# SELE_async_v0_1.net
KiCad netlist of a schematic drawn in EasyEDA
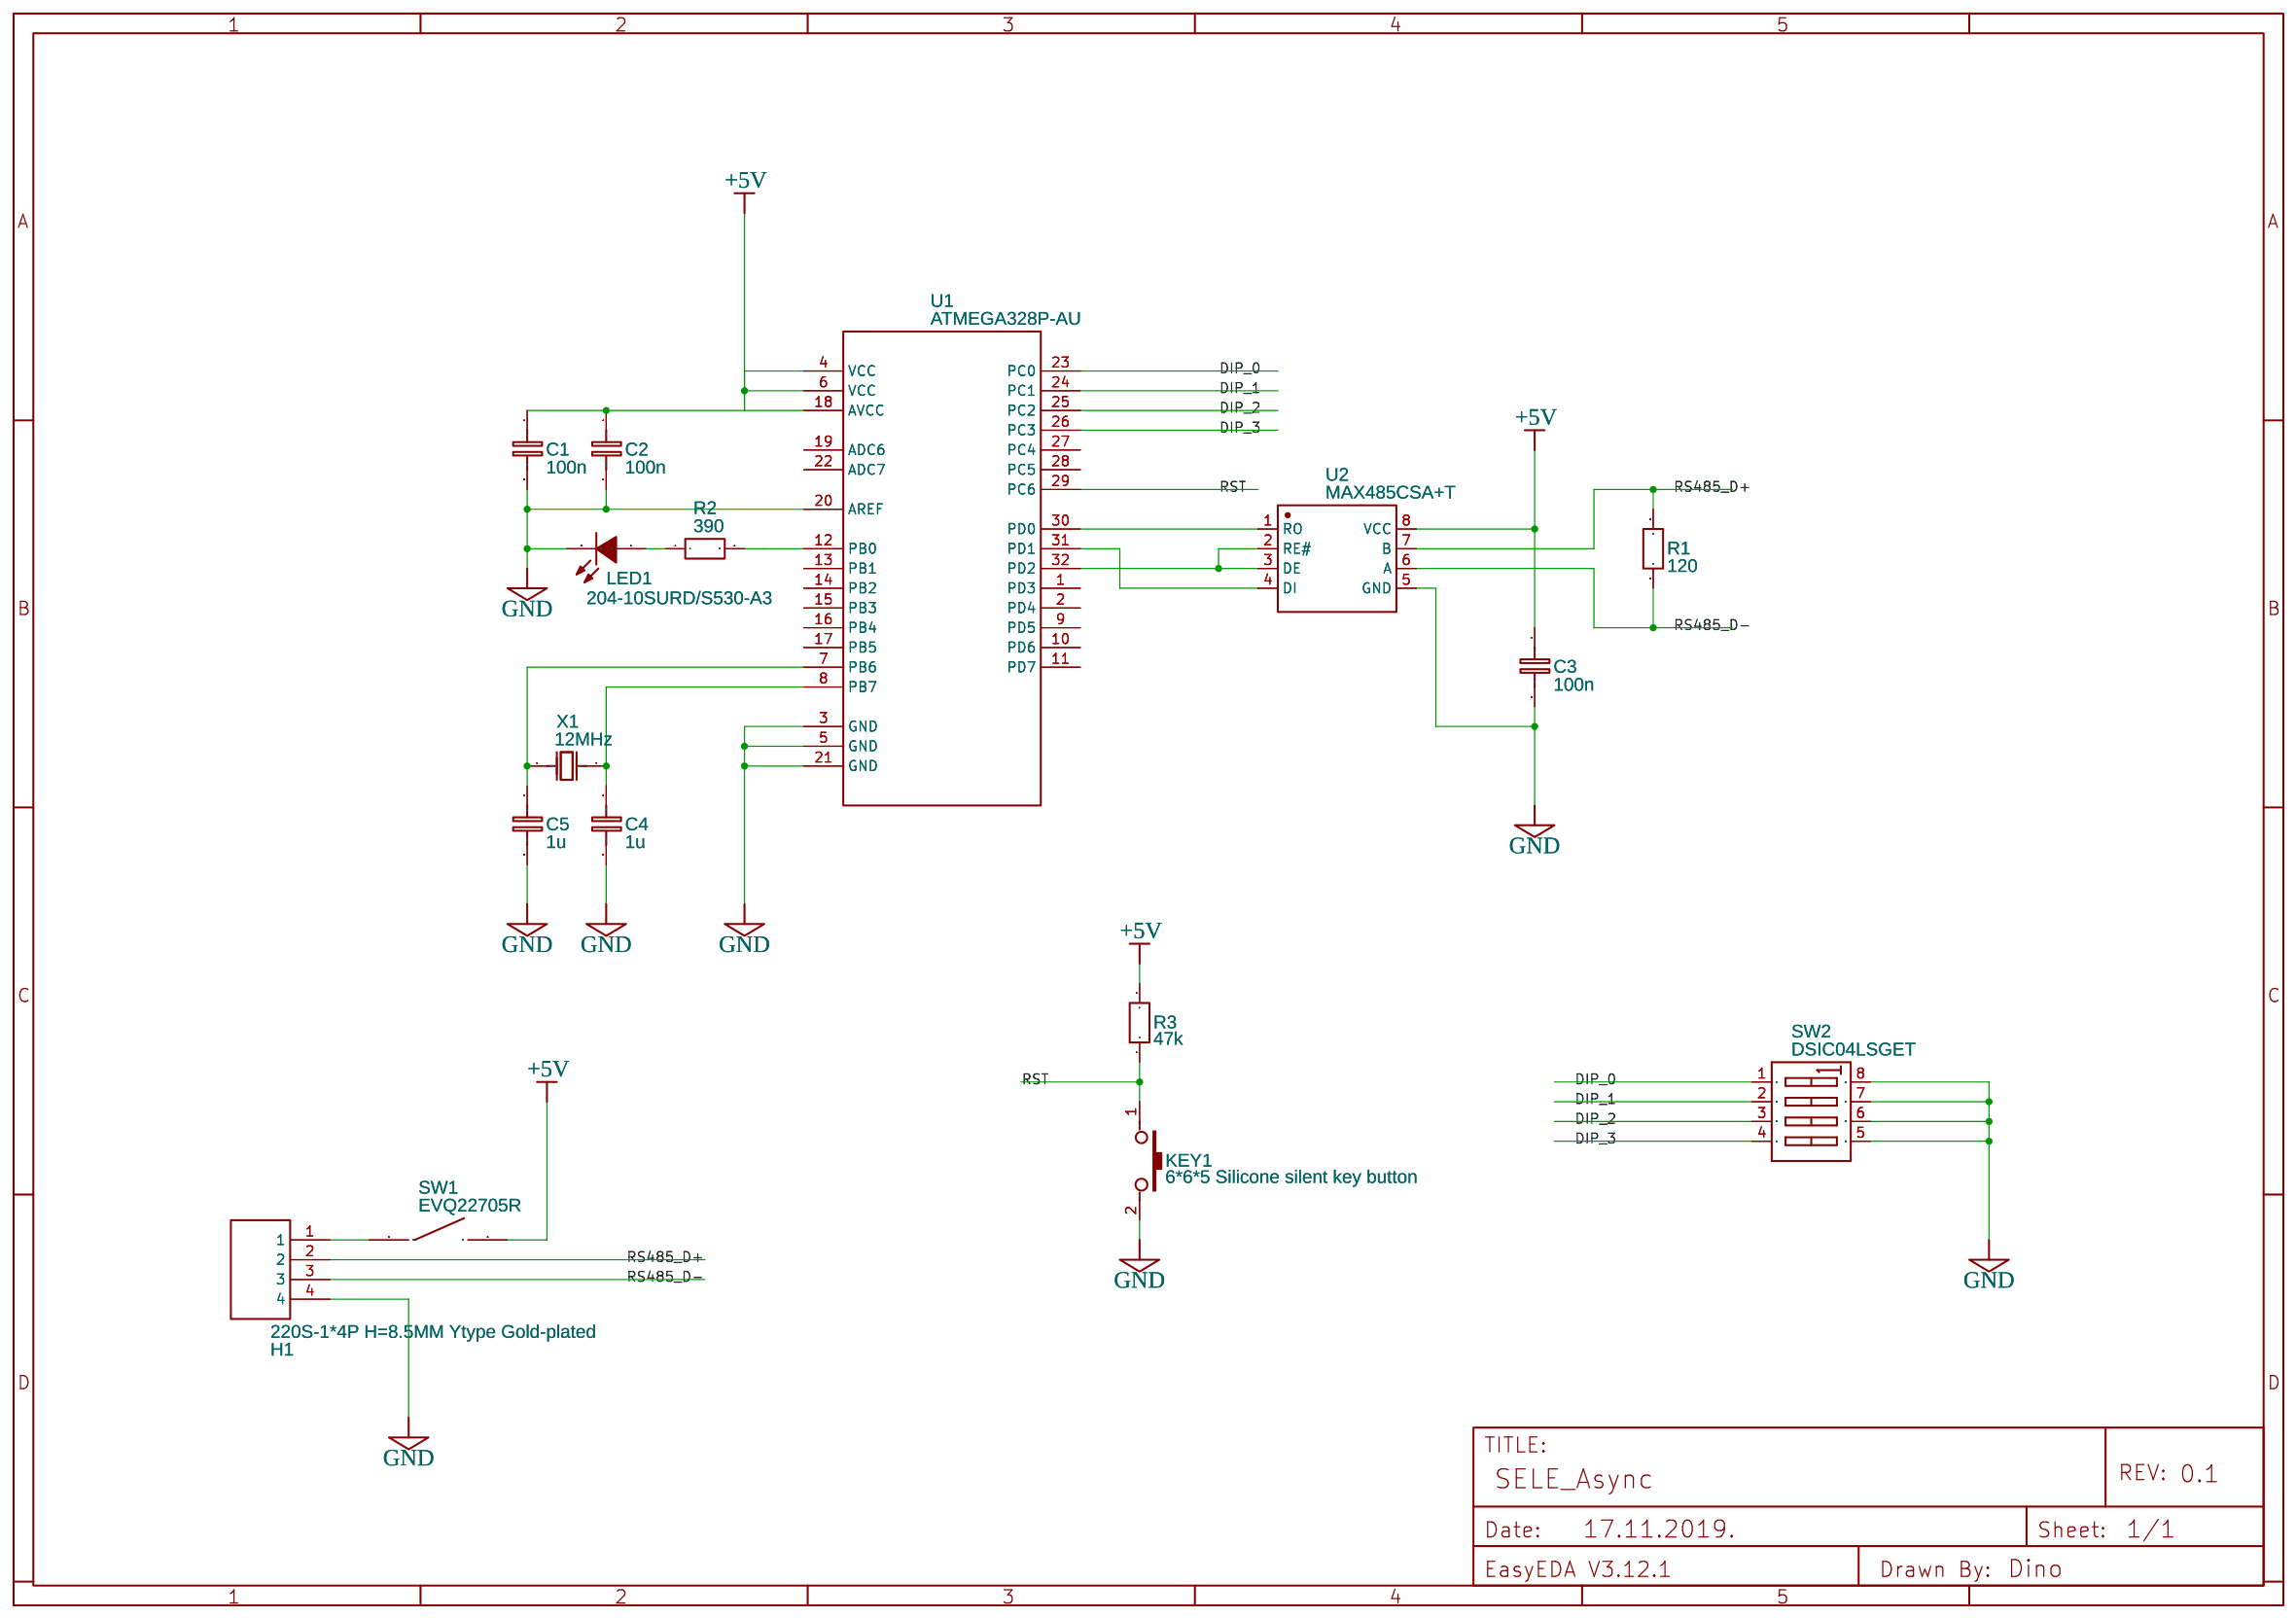
[diagram p0: schematic sheet]

(export (version "E")
  (design (tool "Eeschema 10.0.6"))
  (components
    (comp (ref "C1") (value "100n") (libsource (lib "") (part "Cap_0603_EU")))
    (comp (ref "C2") (value "100n") (libsource (lib "") (part "Cap_0603_EU")))
    (comp (ref "C3") (value "100n") (libsource (lib "") (part "Cap_0603_EU_1")))
    (comp (ref "C4") (value "1u") (libsource (lib "") (part "Cap_0603_EU")))
    (comp (ref "C5") (value "1u") (libsource (lib "") (part "Cap_0603_EU")))
    (comp (ref "H1")
      (value "220S-1*4P H=8.5MM Ytype Gold-plated")
      (fields (field (name "BOM_Supplier Part") "C124413"))
      (libsource (lib "") (part "Unknown_180_670"))
    )
    (comp (ref "KEY1")
      (value "6*6*5 Silicone silent key button")
      (fields (field (name "BOM_Supplier Part") "C61120"))
      (libsource (lib "") (part "Unknown_620_610"))
    )
    (comp (ref "LED1")
      (value "204-10SURD/S530-A3")
      (fields (field (name "BOM_Supplier Part") "C99772"))
      (libsource (lib "") (part "Unknown_350_300"))
    )
    (comp (ref "R1") (value "120") (libsource (lib "") (part "Res_0603(1/10W)_EU")))
    (comp (ref "R2") (value "390") (libsource (lib "") (part "Res_0603(1/10W)_EU_1")))
    (comp (ref "R3") (value "47k") (libsource (lib "") (part "Res_0603(1/10W)_EU")))
    (comp (ref "SW1")
      (value "EVQ22705R")
      (fields (field (name "BOM_Supplier Part") "C79156"))
      (libsource (lib "") (part "Unknown_270_650"))
    )
    (comp (ref "SW2")
      (value "DSIC04LSGET")
      (fields (field (name "BOM_Supplier Part") "C54950"))
      (libsource (lib "") (part "Unknown_960_590"))
    )
    (comp (ref "U1")
      (value "ATMEGA328P-AU")
      (fields (field (name "BOM_Supplier Part") "C14877"))
      (libsource (lib "") (part "Unknown_520_310"))
    )
    (comp (ref "U2")
      (value "MAX485CSA+T")
      (fields (field (name "BOM_Supplier Part") "C9945"))
      (libsource (lib "") (part "Unknown_720_310"))
    )
    (comp (ref "X1")
      (value "12MHz")
      (fields
        (field (name "BOM_Manufacturer Part") "X49SD12MSD2SC")
        (field (name "BOM_Supplier Part") "C16369")
      )
      (libsource (lib "") (part "X49SD12MSD2SC"))
    )
  )
  (nets
    (net (code "1") (name "+5V") (class "Default")
      (node (ref "C1") (pin "1") (pinfunction "1_1") (pintype "unspecified"))
      (node (ref "C2") (pin "1") (pinfunction "1_1") (pintype "unspecified"))
      (node (ref "C3") (pin "1") (pinfunction "1_1") (pintype "unspecified"))
      (node (ref "R3") (pin "2") (pinfunction "2_2") (pintype "unspecified"))
      (node (ref "SW1") (pin "2") (pinfunction "2_2") (pintype "input"))
      (node (ref "U1") (pin "18") (pinfunction "AVCC_18") (pintype "passive"))
      (node (ref "U1") (pin "4") (pinfunction "VCC_4") (pintype "passive"))
      (node (ref "U1") (pin "6") (pinfunction "VCC_6") (pintype "passive"))
      (node (ref "U2") (pin "8") (pinfunction "VCC_8") (pintype "unspecified"))
    )
    (net (code "2") (name "/DIP_0") (class "Default")
      (node (ref "SW2") (pin "1") (pinfunction "A1_1") (pintype "input"))
      (node (ref "U1") (pin "23") (pinfunction "PC0_23") (pintype "unspecified"))
    )
    (net (code "3") (name "/DIP_1") (class "Default")
      (node (ref "SW2") (pin "2") (pinfunction "A2_2") (pintype "input"))
      (node (ref "U1") (pin "24") (pinfunction "PC1_24") (pintype "unspecified"))
    )
    (net (code "4") (name "/DIP_2") (class "Default")
      (node (ref "SW2") (pin "3") (pinfunction "A3_3") (pintype "input"))
      (node (ref "U1") (pin "25") (pinfunction "PC2_25") (pintype "unspecified"))
    )
    (net (code "5") (name "/DIP_3") (class "Default")
      (node (ref "SW2") (pin "4") (pinfunction "A4_4") (pintype "input"))
      (node (ref "U1") (pin "26") (pinfunction "PC3_26") (pintype "unspecified"))
    )
    (net (code "6") (name "/RS485_D+") (class "Default")
      (node (ref "H1") (pin "2") (pinfunction "2_2") (pintype "unspecified"))
      (node (ref "R1") (pin "2") (pinfunction "2_2") (pintype "unspecified"))
      (node (ref "U2") (pin "7") (pinfunction "B_7") (pintype "unspecified"))
    )
    (net (code "7") (name "/RS485_D-") (class "Default")
      (node (ref "H1") (pin "3") (pinfunction "3_3") (pintype "unspecified"))
      (node (ref "R1") (pin "1") (pinfunction "1_1") (pintype "unspecified"))
      (node (ref "U2") (pin "6") (pinfunction "A_6") (pintype "unspecified"))
    )
    (net (code "8") (name "/RST") (class "Default")
      (node (ref "KEY1") (pin "1") (pinfunction "1_1") (pintype "input"))
      (node (ref "R3") (pin "1") (pinfunction "1_1") (pintype "unspecified"))
      (node (ref "U1") (pin "29") (pinfunction "PC6_29") (pintype "unspecified"))
    )
    (net (code "9") (name "GND") (class "Default")
      (node (ref "C1") (pin "2") (pinfunction "2_2") (pintype "unspecified"))
      (node (ref "C2") (pin "2") (pinfunction "2_2") (pintype "unspecified"))
      (node (ref "C3") (pin "2") (pinfunction "2_2") (pintype "unspecified"))
      (node (ref "C4") (pin "2") (pinfunction "2_2") (pintype "unspecified"))
      (node (ref "C5") (pin "2") (pinfunction "2_2") (pintype "unspecified"))
      (node (ref "H1") (pin "4") (pinfunction "4_4") (pintype "unspecified"))
      (node (ref "KEY1") (pin "2") (pinfunction "2_2") (pintype "input"))
      (node (ref "LED1") (pin "2") (pinfunction "K_2") (pintype "unspecified"))
      (node (ref "SW2") (pin "5") (pinfunction "B4_5") (pintype "input"))
      (node (ref "SW2") (pin "6") (pinfunction "B3_6") (pintype "input"))
      (node (ref "SW2") (pin "7") (pinfunction "B2_7") (pintype "input"))
      (node (ref "SW2") (pin "8") (pinfunction "B1_8") (pintype "input"))
      (node (ref "U1") (pin "20") (pinfunction "AREF_20") (pintype "input"))
      (node (ref "U1") (pin "21") (pinfunction "GND_21") (pintype "unspecified"))
      (node (ref "U1") (pin "3") (pinfunction "GND_3") (pintype "unspecified"))
      (node (ref "U1") (pin "5") (pinfunction "GND_5") (pintype "unspecified"))
      (node (ref "U2") (pin "5") (pinfunction "GND_5") (pintype "unspecified"))
    )
    (net (code "10") (name "Net-(H1-Pad1)") (class "Default")
      (node (ref "H1") (pin "1") (pinfunction "1_1") (pintype "unspecified"))
      (node (ref "SW1") (pin "1") (pinfunction "1_1") (pintype "input"))
    )
    (net (code "11") (name "Net-(LED1-A)") (class "Default")
      (node (ref "LED1") (pin "1") (pinfunction "A_1") (pintype "unspecified"))
      (node (ref "R2") (pin "1") (pinfunction "1_1") (pintype "unspecified"))
    )
    (net (code "12") (name "Net-(U1-PB0)") (class "Default")
      (node (ref "R2") (pin "2") (pinfunction "2_2") (pintype "unspecified"))
      (node (ref "U1") (pin "12") (pinfunction "PB0_12") (pintype "unspecified"))
    )
    (net (code "13") (name "Net-(U1-PB6)") (class "Default")
      (node (ref "C5") (pin "1") (pinfunction "1_1") (pintype "unspecified"))
      (node (ref "U1") (pin "7") (pinfunction "PB6_7") (pintype "unspecified"))
      (node (ref "X1") (pin "2") (pinfunction "OSC2_2") (pintype "input"))
    )
    (net (code "14") (name "Net-(U1-PB7)") (class "Default")
      (node (ref "C4") (pin "1") (pinfunction "1_1") (pintype "unspecified"))
      (node (ref "U1") (pin "8") (pinfunction "PB7_8") (pintype "unspecified"))
      (node (ref "X1") (pin "1") (pinfunction "OSC1_1") (pintype "input"))
    )
    (net (code "15") (name "Net-(U1-PD0)") (class "Default")
      (node (ref "U1") (pin "30") (pinfunction "PD0_30") (pintype "unspecified"))
      (node (ref "U2") (pin "1") (pinfunction "RO_1") (pintype "unspecified"))
    )
    (net (code "16") (name "Net-(U1-PD1)") (class "Default")
      (node (ref "U1") (pin "31") (pinfunction "PD1_31") (pintype "unspecified"))
      (node (ref "U2") (pin "4") (pinfunction "DI_4") (pintype "unspecified"))
    )
    (net (code "17") (name "Net-(U1-PD2)") (class "Default")
      (node (ref "U1") (pin "32") (pinfunction "PD2_32") (pintype "unspecified"))
      (node (ref "U2") (pin "2") (pinfunction "RE#_2") (pintype "unspecified"))
      (node (ref "U2") (pin "3") (pinfunction "DE_3") (pintype "unspecified"))
    )
    (net (code "18") (name "unconnected-(U1-ADC6-Pad19)") (class "Default")
      (node (ref "U1") (pin "19") (pinfunction "ADC6_19") (pintype "input"))
    )
    (net (code "19") (name "unconnected-(U1-ADC7-Pad22)") (class "Default")
      (node (ref "U1") (pin "22") (pinfunction "ADC7_22") (pintype "input"))
    )
    (net (code "20") (name "unconnected-(U1-PB1-Pad13)") (class "Default")
      (node (ref "U1") (pin "13") (pinfunction "PB1_13") (pintype "unspecified"))
    )
    (net (code "21") (name "unconnected-(U1-PB2-Pad14)") (class "Default")
      (node (ref "U1") (pin "14") (pinfunction "PB2_14") (pintype "unspecified"))
    )
    (net (code "22") (name "unconnected-(U1-PB3-Pad15)") (class "Default")
      (node (ref "U1") (pin "15") (pinfunction "PB3_15") (pintype "unspecified"))
    )
    (net (code "23") (name "unconnected-(U1-PB4-Pad16)") (class "Default")
      (node (ref "U1") (pin "16") (pinfunction "PB4_16") (pintype "unspecified"))
    )
    (net (code "24") (name "unconnected-(U1-PB5-Pad17)") (class "Default")
      (node (ref "U1") (pin "17") (pinfunction "PB5_17") (pintype "unspecified"))
    )
    (net (code "25") (name "unconnected-(U1-PC4-Pad27)") (class "Default")
      (node (ref "U1") (pin "27") (pinfunction "PC4_27") (pintype "unspecified"))
    )
    (net (code "26") (name "unconnected-(U1-PC5-Pad28)") (class "Default")
      (node (ref "U1") (pin "28") (pinfunction "PC5_28") (pintype "unspecified"))
    )
    (net (code "27") (name "unconnected-(U1-PD3-Pad1)") (class "Default")
      (node (ref "U1") (pin "1") (pinfunction "PD3_1") (pintype "unspecified"))
    )
    (net (code "28") (name "unconnected-(U1-PD4-Pad2)") (class "Default")
      (node (ref "U1") (pin "2") (pinfunction "PD4_2") (pintype "unspecified"))
    )
    (net (code "29") (name "unconnected-(U1-PD5-Pad9)") (class "Default")
      (node (ref "U1") (pin "9") (pinfunction "PD5_9") (pintype "unspecified"))
    )
    (net (code "30") (name "unconnected-(U1-PD6-Pad10)") (class "Default")
      (node (ref "U1") (pin "10") (pinfunction "PD6_10") (pintype "unspecified"))
    )
    (net (code "31") (name "unconnected-(U1-PD7-Pad11)") (class "Default")
      (node (ref "U1") (pin "11") (pinfunction "PD7_11") (pintype "unspecified"))
    )
  )
)
